# Sheet1.net
KiCad netlist of a schematic drawn in Altium Designer
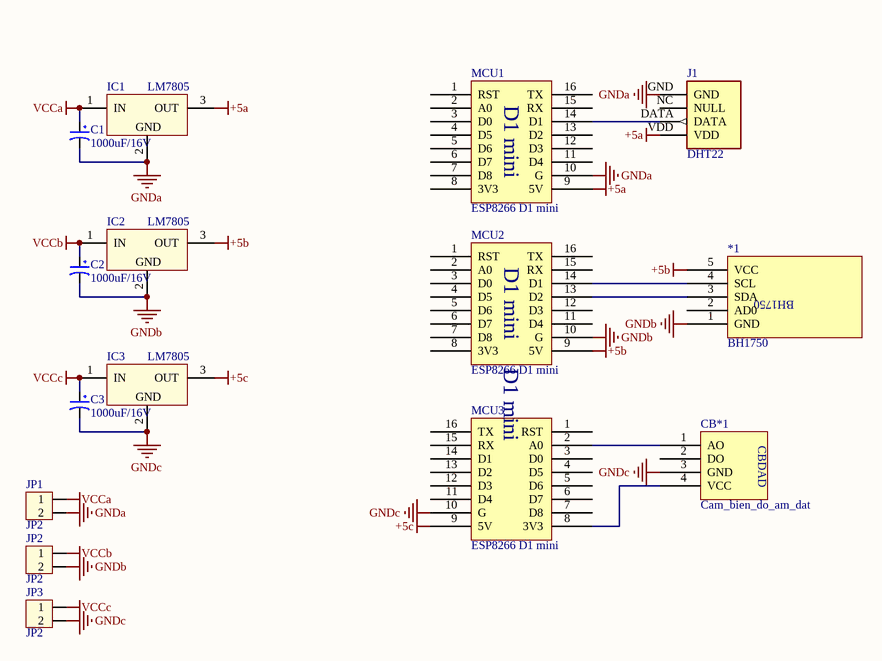
[diagram p0: Sheet1.SchDoc]

(export (version "E")
  (design (tool "Eeschema 10.0.6"))
  (components
    (comp (ref "*1") (value "BH1750") (footprint "BH1750") (libsource (lib "MY_LIBRARY") (part "BH1750")))
    (comp (ref "C1")
      (value "1000uF/16V")
      (footprint "CP1.5/3.4")
      (description "Cap 1000uF/16V - 220uF/50V")
      (libsource (lib "Thuvien3D") (part "CP4"))
    )
    (comp (ref "C2")
      (value "1000uF/16V")
      (footprint "CP1.5/3.4")
      (description "Cap 1000uF/16V - 220uF/50V")
      (libsource (lib "Thuvien3D") (part "CP4"))
    )
    (comp (ref "C3")
      (value "1000uF/16V")
      (footprint "CP1.5/3.4")
      (description "Cap 1000uF/16V - 220uF/50V")
      (libsource (lib "Thuvien3D") (part "CP4"))
    )
    (comp (ref "CB*1")
      (value "Cam_bien_do_am_dat")
      (footprint "Am dat")
      (libsource (lib "MY_LIBRARY") (part "Cam_bien_do_am_dat"))
    )
    (comp (ref "IC1")
      (value "LM7805")
      (footprint "QTO-220")
      (description "On ap +, from + 5 to + 24VDC")
      (libsource (lib "MY_LIBRARY") (part "LM78xx"))
    )
    (comp (ref "IC2")
      (value "LM7805")
      (footprint "QTO-220")
      (description "On ap +, from + 5 to + 24VDC")
      (libsource (lib "MY_LIBRARY") (part "LM78xx"))
    )
    (comp (ref "IC3")
      (value "LM7805")
      (footprint "QTO-220")
      (description "On ap +, from + 5 to + 24VDC")
      (libsource (lib "MY_LIBRARY") (part "LM78xx"))
    )
    (comp (ref "J1")
      (value "DHT22")
      (footprint "DHT22")
      (description "Capacitive-type humidity and temperature module/sensor")
      (fields (field (name "MF") "Aosong Electronics"))
      (libsource (lib "MY_LIBRARY") (part "DHT22"))
    )
    (comp (ref "JP1")
      (value "JP2")
      (footprint "CON2")
      (description "Connector 2")
      (libsource (lib "Thuvien3D") (part "Con2"))
    )
    (comp (ref "JP2")
      (value "JP2")
      (footprint "CON2")
      (description "Connector 2")
      (libsource (lib "Thuvien3D") (part "Con2"))
    )
    (comp (ref "JP3")
      (value "JP2")
      (footprint "CON2")
      (description "Connector 2")
      (libsource (lib "Thuvien3D") (part "Con2"))
    )
    (comp (ref "MCU1")
      (value "ESP8266 D1 mini")
      (footprint "ESP D1 mini")
      (libsource (lib "MY_LIBRARY") (part "ESP8266 D1 mini"))
    )
    (comp (ref "MCU2")
      (value "ESP8266 D1 mini")
      (footprint "ESP D1 mini")
      (libsource (lib "MY_LIBRARY") (part "ESP8266 D1 mini"))
    )
    (comp (ref "MCU3")
      (value "ESP8266 D1 mini")
      (footprint "ESP D1 mini")
      (libsource (lib "") (part "ESP8266 D1 mini_1"))
    )
  )
  (nets
    (net (code "1") (name "+5a") (class "Default")
      (node (ref "IC1") (pin "3") (pinfunction "OUT_3") (pintype "passive"))
      (node (ref "J1") (pin "VDD") (pinfunction "VDD_VDD") (pintype "power_in"))
      (node (ref "MCU1") (pin "9") (pinfunction "5V_9") (pintype "passive"))
    )
    (net (code "2") (name "+5b") (class "Default")
      (node (ref "*1") (pin "5") (pinfunction "VCC_5") (pintype "passive"))
      (node (ref "IC2") (pin "3") (pinfunction "OUT_3") (pintype "passive"))
      (node (ref "MCU2") (pin "9") (pinfunction "5V_9") (pintype "passive"))
    )
    (net (code "3") (name "+5c") (class "Default")
      (node (ref "IC3") (pin "3") (pinfunction "OUT_3") (pintype "passive"))
      (node (ref "MCU3") (pin "9") (pinfunction "5V_9") (pintype "passive"))
    )
    (net (code "4") (name "GNDa") (class "Default")
      (node (ref "C1") (pin "2") (pinfunction "2_2") (pintype "passive"))
      (node (ref "IC1") (pin "2") (pinfunction "GND_2") (pintype "passive"))
      (node (ref "J1") (pin "GND") (pinfunction "GND_GND") (pintype "power_in"))
      (node (ref "JP1") (pin "2") (pinfunction "2_2") (pintype "passive"))
      (node (ref "MCU1") (pin "10") (pinfunction "G_10") (pintype "passive"))
    )
    (net (code "5") (name "GNDb") (class "Default")
      (node (ref "*1") (pin "1") (pinfunction "GND_1") (pintype "passive"))
      (node (ref "C2") (pin "2") (pinfunction "2_2") (pintype "passive"))
      (node (ref "IC2") (pin "2") (pinfunction "GND_2") (pintype "passive"))
      (node (ref "JP2") (pin "2") (pinfunction "2_2") (pintype "passive"))
      (node (ref "MCU2") (pin "10") (pinfunction "G_10") (pintype "passive"))
    )
    (net (code "6") (name "GNDc") (class "Default")
      (node (ref "C3") (pin "2") (pinfunction "2_2") (pintype "passive"))
      (node (ref "CB*1") (pin "3") (pinfunction "GND_3") (pintype "passive"))
      (node (ref "IC3") (pin "2") (pinfunction "GND_2") (pintype "passive"))
      (node (ref "JP3") (pin "2") (pinfunction "2_2") (pintype "passive"))
      (node (ref "MCU3") (pin "10") (pinfunction "G_10") (pintype "passive"))
    )
    (net (code "7") (name "Net-(*1-SCL)") (class "Default")
      (node (ref "*1") (pin "4") (pinfunction "SCL_4") (pintype "passive"))
      (node (ref "MCU2") (pin "14") (pinfunction "D1_14") (pintype "passive"))
    )
    (net (code "8") (name "Net-(*1-SDA)") (class "Default")
      (node (ref "*1") (pin "3") (pinfunction "SDA_3") (pintype "passive"))
      (node (ref "MCU2") (pin "13") (pinfunction "D2_13") (pintype "passive"))
    )
    (net (code "9") (name "Net-(CB*1-AO)") (class "Default")
      (node (ref "CB*1") (pin "1") (pinfunction "AO_1") (pintype "passive"))
      (node (ref "MCU3") (pin "2") (pinfunction "A0_2") (pintype "passive"))
    )
    (net (code "10") (name "Net-(CB*1-VCC)") (class "Default")
      (node (ref "CB*1") (pin "4") (pinfunction "VCC_4") (pintype "passive"))
      (node (ref "MCU3") (pin "8") (pinfunction "3V3_8") (pintype "passive"))
    )
    (net (code "11") (name "Net-(MCU1-D1)") (class "Default")
      (node (ref "J1") (pin "DATA") (pinfunction "DATA_DATA") (pintype "output"))
      (node (ref "MCU1") (pin "14") (pinfunction "D1_14") (pintype "passive"))
    )
    (net (code "12") (name "VCCa") (class "Default")
      (node (ref "C1") (pin "1") (pinfunction "1_1") (pintype "passive"))
      (node (ref "IC1") (pin "1") (pinfunction "IN_1") (pintype "passive"))
      (node (ref "JP1") (pin "1") (pinfunction "1_1") (pintype "passive"))
    )
    (net (code "13") (name "VCCb") (class "Default")
      (node (ref "C2") (pin "1") (pinfunction "1_1") (pintype "passive"))
      (node (ref "IC2") (pin "1") (pinfunction "IN_1") (pintype "passive"))
      (node (ref "JP2") (pin "1") (pinfunction "1_1") (pintype "passive"))
    )
    (net (code "14") (name "VCCc") (class "Default")
      (node (ref "C3") (pin "1") (pinfunction "1_1") (pintype "passive"))
      (node (ref "IC3") (pin "1") (pinfunction "IN_1") (pintype "passive"))
      (node (ref "JP3") (pin "1") (pinfunction "1_1") (pintype "passive"))
    )
    (net (code "15") (name "unconnected-(*1-AD0-Pad2)") (class "Default")
      (node (ref "*1") (pin "2") (pinfunction "AD0_2") (pintype "passive"))
    )
    (net (code "16") (name "unconnected-(CB*1-DO-Pad2)") (class "Default")
      (node (ref "CB*1") (pin "2") (pinfunction "DO_2") (pintype "passive"))
    )
    (net (code "17") (name "unconnected-(J1-NULL-PadNC)") (class "Default")
      (node (ref "J1") (pin "NC") (pinfunction "NULL_NC") (pintype "passive"))
    )
    (net (code "18") (name "unconnected-(MCU1-3V3-Pad8)") (class "Default")
      (node (ref "MCU1") (pin "8") (pinfunction "3V3_8") (pintype "passive"))
    )
    (net (code "19") (name "unconnected-(MCU1-A0-Pad2)") (class "Default")
      (node (ref "MCU1") (pin "2") (pinfunction "A0_2") (pintype "passive"))
    )
    (net (code "20") (name "unconnected-(MCU1-D0-Pad3)") (class "Default")
      (node (ref "MCU1") (pin "3") (pinfunction "D0_3") (pintype "passive"))
    )
    (net (code "21") (name "unconnected-(MCU1-D2-Pad13)") (class "Default")
      (node (ref "MCU1") (pin "13") (pinfunction "D2_13") (pintype "passive"))
    )
    (net (code "22") (name "unconnected-(MCU1-D3-Pad12)") (class "Default")
      (node (ref "MCU1") (pin "12") (pinfunction "D3_12") (pintype "passive"))
    )
    (net (code "23") (name "unconnected-(MCU1-D4-Pad11)") (class "Default")
      (node (ref "MCU1") (pin "11") (pinfunction "D4_11") (pintype "passive"))
    )
    (net (code "24") (name "unconnected-(MCU1-D5-Pad4)") (class "Default")
      (node (ref "MCU1") (pin "4") (pinfunction "D5_4") (pintype "passive"))
    )
    (net (code "25") (name "unconnected-(MCU1-D6-Pad5)") (class "Default")
      (node (ref "MCU1") (pin "5") (pinfunction "D6_5") (pintype "passive"))
    )
    (net (code "26") (name "unconnected-(MCU1-D7-Pad6)") (class "Default")
      (node (ref "MCU1") (pin "6") (pinfunction "D7_6") (pintype "passive"))
    )
    (net (code "27") (name "unconnected-(MCU1-D8-Pad7)") (class "Default")
      (node (ref "MCU1") (pin "7") (pinfunction "D8_7") (pintype "passive"))
    )
    (net (code "28") (name "unconnected-(MCU1-RST-Pad1)") (class "Default")
      (node (ref "MCU1") (pin "1") (pinfunction "RST_1") (pintype "passive"))
    )
    (net (code "29") (name "unconnected-(MCU1-RX-Pad15)") (class "Default")
      (node (ref "MCU1") (pin "15") (pinfunction "RX_15") (pintype "passive"))
    )
    (net (code "30") (name "unconnected-(MCU1-TX-Pad16)") (class "Default")
      (node (ref "MCU1") (pin "16") (pinfunction "TX_16") (pintype "passive"))
    )
    (net (code "31") (name "unconnected-(MCU2-3V3-Pad8)") (class "Default")
      (node (ref "MCU2") (pin "8") (pinfunction "3V3_8") (pintype "passive"))
    )
    (net (code "32") (name "unconnected-(MCU2-A0-Pad2)") (class "Default")
      (node (ref "MCU2") (pin "2") (pinfunction "A0_2") (pintype "passive"))
    )
    (net (code "33") (name "unconnected-(MCU2-D0-Pad3)") (class "Default")
      (node (ref "MCU2") (pin "3") (pinfunction "D0_3") (pintype "passive"))
    )
    (net (code "34") (name "unconnected-(MCU2-D3-Pad12)") (class "Default")
      (node (ref "MCU2") (pin "12") (pinfunction "D3_12") (pintype "passive"))
    )
    (net (code "35") (name "unconnected-(MCU2-D4-Pad11)") (class "Default")
      (node (ref "MCU2") (pin "11") (pinfunction "D4_11") (pintype "passive"))
    )
    (net (code "36") (name "unconnected-(MCU2-D5-Pad4)") (class "Default")
      (node (ref "MCU2") (pin "4") (pinfunction "D5_4") (pintype "passive"))
    )
    (net (code "37") (name "unconnected-(MCU2-D6-Pad5)") (class "Default")
      (node (ref "MCU2") (pin "5") (pinfunction "D6_5") (pintype "passive"))
    )
    (net (code "38") (name "unconnected-(MCU2-D7-Pad6)") (class "Default")
      (node (ref "MCU2") (pin "6") (pinfunction "D7_6") (pintype "passive"))
    )
    (net (code "39") (name "unconnected-(MCU2-D8-Pad7)") (class "Default")
      (node (ref "MCU2") (pin "7") (pinfunction "D8_7") (pintype "passive"))
    )
    (net (code "40") (name "unconnected-(MCU2-RST-Pad1)") (class "Default")
      (node (ref "MCU2") (pin "1") (pinfunction "RST_1") (pintype "passive"))
    )
    (net (code "41") (name "unconnected-(MCU2-RX-Pad15)") (class "Default")
      (node (ref "MCU2") (pin "15") (pinfunction "RX_15") (pintype "passive"))
    )
    (net (code "42") (name "unconnected-(MCU2-TX-Pad16)") (class "Default")
      (node (ref "MCU2") (pin "16") (pinfunction "TX_16") (pintype "passive"))
    )
    (net (code "43") (name "unconnected-(MCU3-D0-Pad3)") (class "Default")
      (node (ref "MCU3") (pin "3") (pinfunction "D0_3") (pintype "passive"))
    )
    (net (code "44") (name "unconnected-(MCU3-D1-Pad14)") (class "Default")
      (node (ref "MCU3") (pin "14") (pinfunction "D1_14") (pintype "passive"))
    )
    (net (code "45") (name "unconnected-(MCU3-D2-Pad13)") (class "Default")
      (node (ref "MCU3") (pin "13") (pinfunction "D2_13") (pintype "passive"))
    )
    (net (code "46") (name "unconnected-(MCU3-D3-Pad12)") (class "Default")
      (node (ref "MCU3") (pin "12") (pinfunction "D3_12") (pintype "passive"))
    )
    (net (code "47") (name "unconnected-(MCU3-D4-Pad11)") (class "Default")
      (node (ref "MCU3") (pin "11") (pinfunction "D4_11") (pintype "passive"))
    )
    (net (code "48") (name "unconnected-(MCU3-D5-Pad4)") (class "Default")
      (node (ref "MCU3") (pin "4") (pinfunction "D5_4") (pintype "passive"))
    )
    (net (code "49") (name "unconnected-(MCU3-D6-Pad5)") (class "Default")
      (node (ref "MCU3") (pin "5") (pinfunction "D6_5") (pintype "passive"))
    )
    (net (code "50") (name "unconnected-(MCU3-D7-Pad6)") (class "Default")
      (node (ref "MCU3") (pin "6") (pinfunction "D7_6") (pintype "passive"))
    )
    (net (code "51") (name "unconnected-(MCU3-D8-Pad7)") (class "Default")
      (node (ref "MCU3") (pin "7") (pinfunction "D8_7") (pintype "passive"))
    )
    (net (code "52") (name "unconnected-(MCU3-RST-Pad1)") (class "Default")
      (node (ref "MCU3") (pin "1") (pinfunction "RST_1") (pintype "passive"))
    )
    (net (code "53") (name "unconnected-(MCU3-RX-Pad15)") (class "Default")
      (node (ref "MCU3") (pin "15") (pinfunction "RX_15") (pintype "passive"))
    )
    (net (code "54") (name "unconnected-(MCU3-TX-Pad16)") (class "Default")
      (node (ref "MCU3") (pin "16") (pinfunction "TX_16") (pintype "passive"))
    )
  )
)
